# motor_board.net
KiCad netlist of a schematic drawn in EAGLE
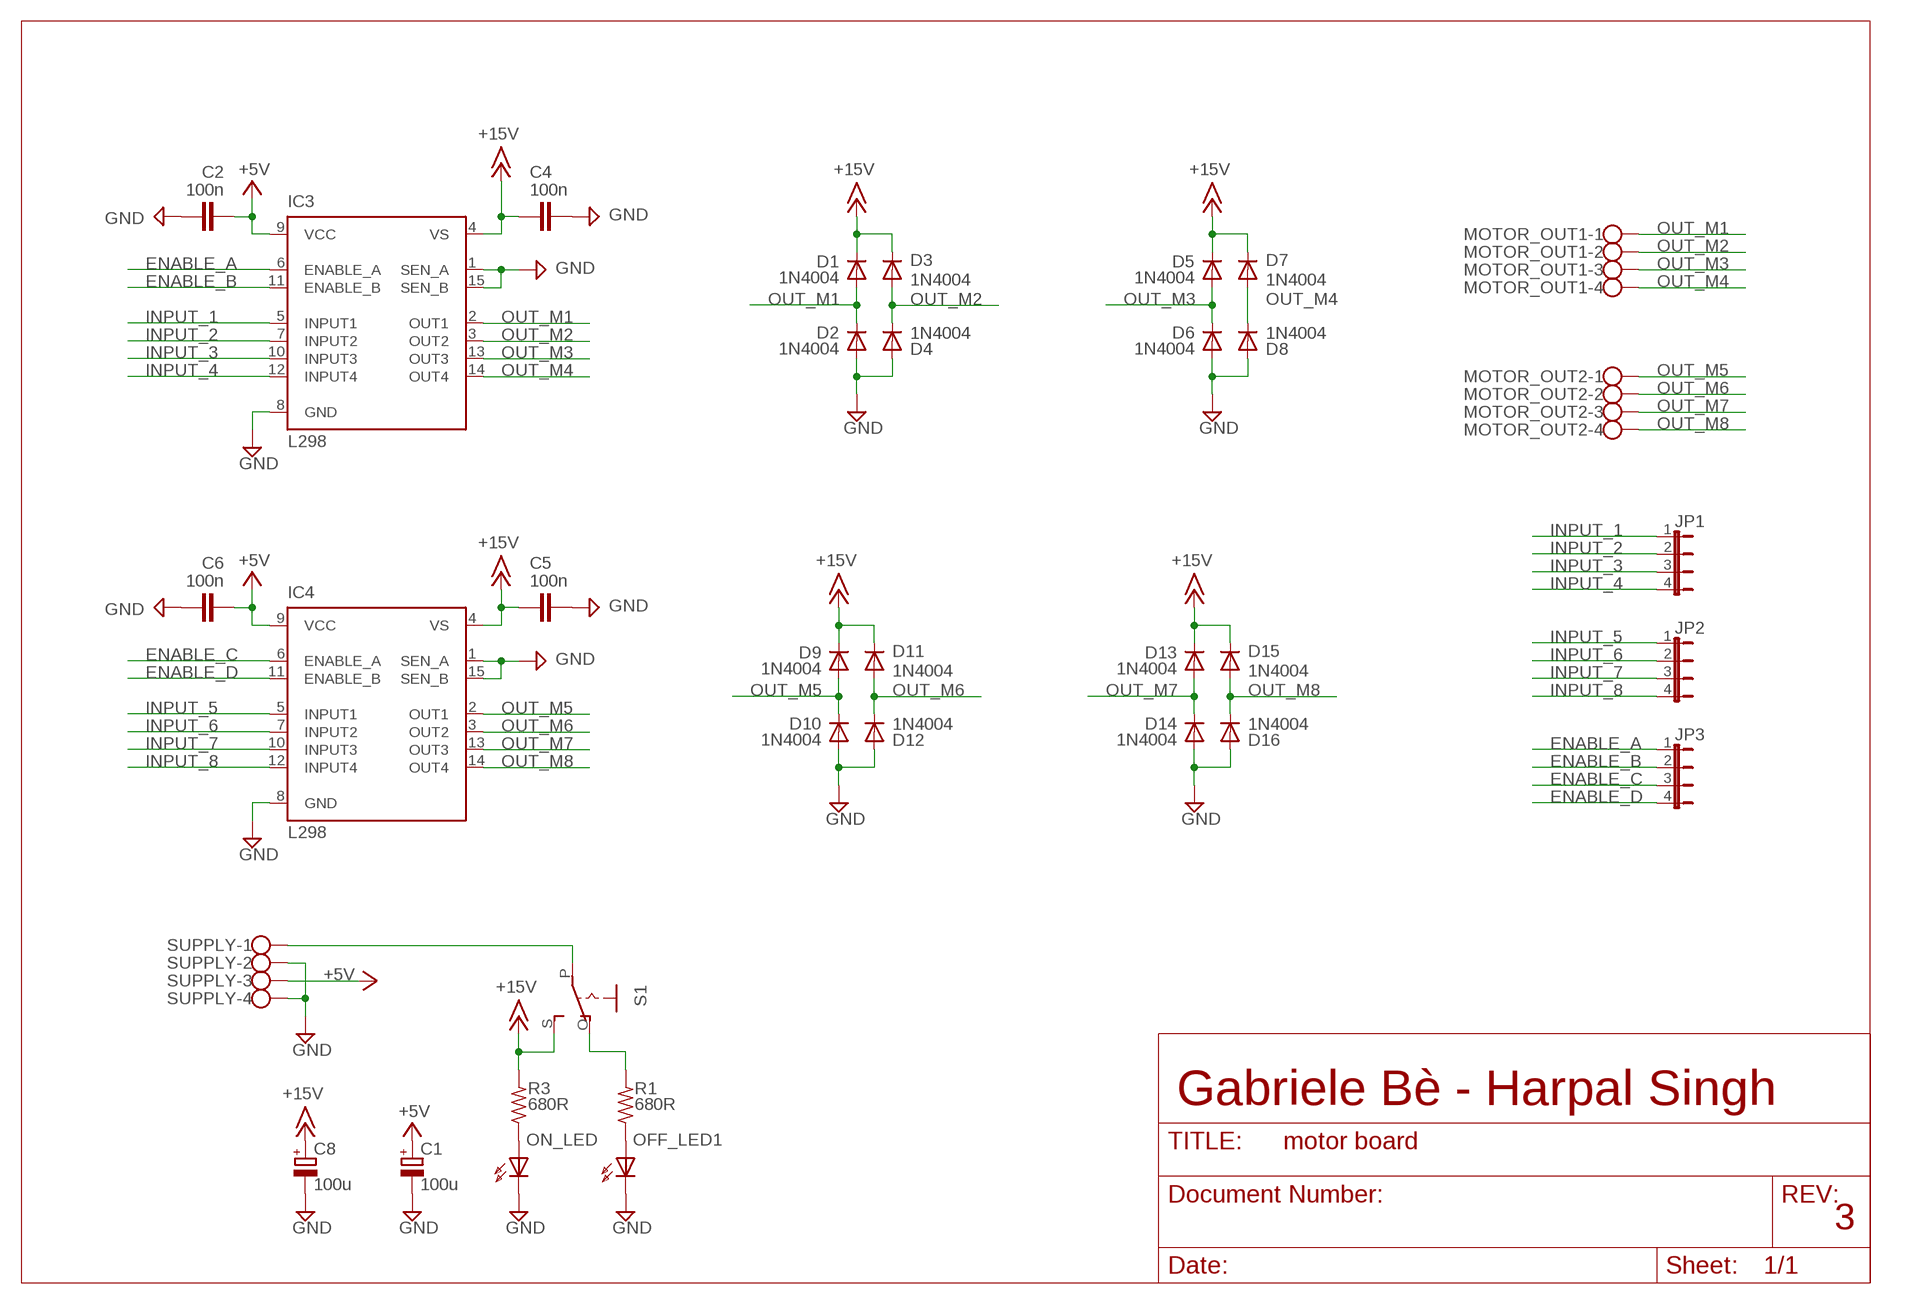
[diagram p0: schematic, sheet 1]

(export (version "E")
  (design (tool "Eeschema 10.0.6"))
  (components
    (comp (ref "C1")
      (value "100u")
      (footprint "eagle-import:E2,5-7")
      (libsource (lib "eagle-import") (part "CPOL-EUE2.5-7"))
    )
    (comp (ref "C2")
      (value "100n")
      (footprint "eagle-import:C050-024X044")
      (libsource (lib "eagle-import") (part "C-EU050-024X044"))
    )
    (comp (ref "C4")
      (value "100n")
      (footprint "eagle-import:C050-024X044")
      (libsource (lib "eagle-import") (part "C-EU050-024X044"))
    )
    (comp (ref "C5")
      (value "100n")
      (footprint "eagle-import:C050-024X044")
      (libsource (lib "eagle-import") (part "C-EU050-024X044"))
    )
    (comp (ref "C6")
      (value "100n")
      (footprint "eagle-import:C050-024X044")
      (libsource (lib "eagle-import") (part "C-EU050-024X044"))
    )
    (comp (ref "C8")
      (value "100u")
      (footprint "eagle-import:E2,5-7")
      (libsource (lib "eagle-import") (part "CPOL-EUE2.5-7"))
    )
    (comp (ref "D1")
      (value "1N4004")
      (footprint "eagle-import:DO41-10")
      (libsource (lib "eagle-import") (part "1N4004"))
    )
    (comp (ref "D2")
      (value "1N4004")
      (footprint "eagle-import:DO41-10")
      (libsource (lib "eagle-import") (part "1N4004"))
    )
    (comp (ref "D3")
      (value "1N4004")
      (footprint "eagle-import:DO41-10")
      (libsource (lib "eagle-import") (part "1N4004"))
    )
    (comp (ref "D4")
      (value "1N4004")
      (footprint "eagle-import:DO41-10")
      (libsource (lib "eagle-import") (part "1N4004"))
    )
    (comp (ref "D5")
      (value "1N4004")
      (footprint "eagle-import:DO41-10")
      (libsource (lib "eagle-import") (part "1N4004"))
    )
    (comp (ref "D6")
      (value "1N4004")
      (footprint "eagle-import:DO41-10")
      (libsource (lib "eagle-import") (part "1N4004"))
    )
    (comp (ref "D7")
      (value "1N4004")
      (footprint "eagle-import:DO41-10")
      (libsource (lib "eagle-import") (part "1N4004"))
    )
    (comp (ref "D8")
      (value "1N4004")
      (footprint "eagle-import:DO41-10")
      (libsource (lib "eagle-import") (part "1N4004"))
    )
    (comp (ref "D9")
      (value "1N4004")
      (footprint "eagle-import:DO41-10")
      (libsource (lib "eagle-import") (part "1N4004"))
    )
    (comp (ref "D10")
      (value "1N4004")
      (footprint "eagle-import:DO41-10")
      (libsource (lib "eagle-import") (part "1N4004"))
    )
    (comp (ref "D11")
      (value "1N4004")
      (footprint "eagle-import:DO41-10")
      (libsource (lib "eagle-import") (part "1N4004"))
    )
    (comp (ref "D12")
      (value "1N4004")
      (footprint "eagle-import:DO41-10")
      (libsource (lib "eagle-import") (part "1N4004"))
    )
    (comp (ref "D13")
      (value "1N4004")
      (footprint "eagle-import:DO41-10")
      (libsource (lib "eagle-import") (part "1N4004"))
    )
    (comp (ref "D14")
      (value "1N4004")
      (footprint "eagle-import:DO41-10")
      (libsource (lib "eagle-import") (part "1N4004"))
    )
    (comp (ref "D15")
      (value "1N4004")
      (footprint "eagle-import:DO41-10")
      (libsource (lib "eagle-import") (part "1N4004"))
    )
    (comp (ref "D16")
      (value "1N4004")
      (footprint "eagle-import:DO41-10")
      (libsource (lib "eagle-import") (part "1N4004"))
    )
    (comp (ref "IC3")
      (value "L298")
      (footprint "eagle-import:MULTIWATT-15")
      (libsource (lib "eagle-import") (part "L298"))
    )
    (comp (ref "IC4")
      (value "L298")
      (footprint "eagle-import:MULTIWATT-15")
      (libsource (lib "eagle-import") (part "L298"))
    )
    (comp (ref "JP1")
      (value "JP4E")
      (footprint "eagle-import:JP4")
      (libsource (lib "eagle-import") (part "JP4E"))
    )
    (comp (ref "JP2")
      (value "JP4E")
      (footprint "eagle-import:JP4")
      (libsource (lib "eagle-import") (part "JP4E"))
    )
    (comp (ref "JP3")
      (value "JP4E")
      (footprint "eagle-import:JP4")
      (libsource (lib "eagle-import") (part "JP4E"))
    )
    (comp (ref "MOTOR_OUT1")
      (value "W237-4")
      (footprint "eagle-import:W237-4")
      (libsource (lib "eagle-import") (part "W237-4"))
    )
    (comp (ref "MOTOR_OUT2")
      (value "W237-4")
      (footprint "eagle-import:W237-4")
      (libsource (lib "eagle-import") (part "W237-4"))
    )
    (comp (ref "OFF_LED1")
      (value "HLMP6")
      (footprint "eagle-import:HLMP6")
      (fields (field (name "MF") "AGILENT TECHNOLOGIES") (field (name "MPN") "HLMP-6500"))
      (libsource (lib "eagle-import") (part "HLMP6"))
    )
    (comp (ref "ON_LED")
      (value "HLMP6")
      (footprint "eagle-import:HLMP6")
      (fields (field (name "MF") "AGILENT TECHNOLOGIES") (field (name "MPN") "HLMP-6500"))
      (libsource (lib "eagle-import") (part "HLMP6"))
    )
    (comp (ref "R1")
      (value "680R")
      (footprint "eagle-import:0207_10")
      (libsource (lib "eagle-import") (part "R-US_0207/10"))
    )
    (comp (ref "R3")
      (value "680R")
      (footprint "eagle-import:0207_10")
      (libsource (lib "eagle-import") (part "R-US_0207/10"))
    )
    (comp (ref "S1")
      (value "EG1218S")
      (footprint "eagle-import:EG1218")
      (libsource (lib "eagle-import") (part "EG1218S"))
    )
    (comp (ref "SUPPLY")
      (value "W237-4")
      (footprint "eagle-import:W237-4")
      (libsource (lib "eagle-import") (part "W237-4"))
    )
  )
  (nets
    (net (code "1") (name "+5V") (class "Default")
      (node (ref "C1") (pin "+") (pinfunction "+_+") (pintype "passive"))
      (node (ref "C2") (pin "2") (pinfunction "2_2") (pintype "passive"))
      (node (ref "C6") (pin "2") (pinfunction "2_2") (pintype "passive"))
      (node (ref "IC3") (pin "9") (pinfunction "VCC_9") (pintype "power_in"))
      (node (ref "IC4") (pin "9") (pinfunction "VCC_9") (pintype "power_in"))
      (node (ref "SUPPLY") (pin "3") (pinfunction "KL_3") (pintype "passive"))
    )
    (net (code "2") (name "+15V") (class "Default")
      (node (ref "C4") (pin "1") (pinfunction "1_1") (pintype "passive"))
      (node (ref "C5") (pin "1") (pinfunction "1_1") (pintype "passive"))
      (node (ref "C8") (pin "+") (pinfunction "+_+") (pintype "passive"))
      (node (ref "D1") (pin "C") (pinfunction "C_C") (pintype "passive"))
      (node (ref "D11") (pin "C") (pinfunction "C_C") (pintype "passive"))
      (node (ref "D13") (pin "C") (pinfunction "C_C") (pintype "passive"))
      (node (ref "D15") (pin "C") (pinfunction "C_C") (pintype "passive"))
      (node (ref "D3") (pin "C") (pinfunction "C_C") (pintype "passive"))
      (node (ref "D5") (pin "C") (pinfunction "C_C") (pintype "passive"))
      (node (ref "D7") (pin "C") (pinfunction "C_C") (pintype "passive"))
      (node (ref "D9") (pin "C") (pinfunction "C_C") (pintype "passive"))
      (node (ref "IC3") (pin "4") (pinfunction "VS_4") (pintype "power_in"))
      (node (ref "IC4") (pin "4") (pinfunction "VS_4") (pintype "power_in"))
      (node (ref "R3") (pin "2") (pinfunction "2_2") (pintype "passive"))
      (node (ref "S1") (pin "S") (pinfunction "S_S") (pintype "passive"))
    )
    (net (code "3") (name "/ENABLE_A") (class "Default")
      (node (ref "IC3") (pin "6") (pinfunction "ENABLE_A_6") (pintype "input"))
      (node (ref "JP3") (pin "1") (pinfunction "1_1") (pintype "passive"))
    )
    (net (code "4") (name "/ENABLE_B") (class "Default")
      (node (ref "IC3") (pin "11") (pinfunction "ENABLE_B_11") (pintype "input"))
      (node (ref "JP3") (pin "2") (pinfunction "2_2") (pintype "passive"))
    )
    (net (code "5") (name "/ENABLE_C") (class "Default")
      (node (ref "IC4") (pin "6") (pinfunction "ENABLE_A_6") (pintype "input"))
      (node (ref "JP3") (pin "3") (pinfunction "3_3") (pintype "passive"))
    )
    (net (code "6") (name "/ENABLE_D") (class "Default")
      (node (ref "IC4") (pin "11") (pinfunction "ENABLE_B_11") (pintype "input"))
      (node (ref "JP3") (pin "4") (pinfunction "4_4") (pintype "passive"))
    )
    (net (code "7") (name "/INPUT_1") (class "Default")
      (node (ref "IC3") (pin "5") (pinfunction "INPUT1_5") (pintype "input"))
      (node (ref "JP1") (pin "1") (pinfunction "1_1") (pintype "passive"))
    )
    (net (code "8") (name "/INPUT_2") (class "Default")
      (node (ref "IC3") (pin "7") (pinfunction "INPUT2_7") (pintype "input"))
      (node (ref "JP1") (pin "2") (pinfunction "2_2") (pintype "passive"))
    )
    (net (code "9") (name "/INPUT_3") (class "Default")
      (node (ref "IC3") (pin "10") (pinfunction "INPUT3_10") (pintype "input"))
      (node (ref "JP1") (pin "3") (pinfunction "3_3") (pintype "passive"))
    )
    (net (code "10") (name "/INPUT_4") (class "Default")
      (node (ref "IC3") (pin "12") (pinfunction "INPUT4_12") (pintype "input"))
      (node (ref "JP1") (pin "4") (pinfunction "4_4") (pintype "passive"))
    )
    (net (code "11") (name "/INPUT_5") (class "Default")
      (node (ref "IC4") (pin "5") (pinfunction "INPUT1_5") (pintype "input"))
      (node (ref "JP2") (pin "1") (pinfunction "1_1") (pintype "passive"))
    )
    (net (code "12") (name "/INPUT_6") (class "Default")
      (node (ref "IC4") (pin "7") (pinfunction "INPUT2_7") (pintype "input"))
      (node (ref "JP2") (pin "2") (pinfunction "2_2") (pintype "passive"))
    )
    (net (code "13") (name "/INPUT_7") (class "Default")
      (node (ref "IC4") (pin "10") (pinfunction "INPUT3_10") (pintype "input"))
      (node (ref "JP2") (pin "3") (pinfunction "3_3") (pintype "passive"))
    )
    (net (code "14") (name "/INPUT_8") (class "Default")
      (node (ref "IC4") (pin "12") (pinfunction "INPUT4_12") (pintype "input"))
      (node (ref "JP2") (pin "4") (pinfunction "4_4") (pintype "passive"))
    )
    (net (code "15") (name "/OUT_M1") (class "Default")
      (node (ref "D1") (pin "A") (pinfunction "A_A") (pintype "passive"))
      (node (ref "D2") (pin "C") (pinfunction "C_C") (pintype "passive"))
      (node (ref "IC3") (pin "2") (pinfunction "OUT1_2") (pintype "output"))
      (node (ref "MOTOR_OUT1") (pin "1") (pinfunction "KL_1") (pintype "passive"))
    )
    (net (code "16") (name "/OUT_M2") (class "Default")
      (node (ref "D3") (pin "A") (pinfunction "A_A") (pintype "passive"))
      (node (ref "D4") (pin "C") (pinfunction "C_C") (pintype "passive"))
      (node (ref "IC3") (pin "3") (pinfunction "OUT2_3") (pintype "output"))
      (node (ref "MOTOR_OUT1") (pin "2") (pinfunction "KL_2") (pintype "passive"))
    )
    (net (code "17") (name "/OUT_M3") (class "Default")
      (node (ref "D5") (pin "A") (pinfunction "A_A") (pintype "passive"))
      (node (ref "D6") (pin "C") (pinfunction "C_C") (pintype "passive"))
      (node (ref "IC3") (pin "13") (pinfunction "OUT3_13") (pintype "output"))
      (node (ref "MOTOR_OUT1") (pin "3") (pinfunction "KL_3") (pintype "passive"))
    )
    (net (code "18") (name "/OUT_M4") (class "Default")
      (node (ref "D7") (pin "A") (pinfunction "A_A") (pintype "passive"))
      (node (ref "D8") (pin "C") (pinfunction "C_C") (pintype "passive"))
      (node (ref "IC3") (pin "14") (pinfunction "OUT4_14") (pintype "output"))
      (node (ref "MOTOR_OUT1") (pin "4") (pinfunction "KL_4") (pintype "passive"))
    )
    (net (code "19") (name "/OUT_M5") (class "Default")
      (node (ref "D10") (pin "C") (pinfunction "C_C") (pintype "passive"))
      (node (ref "D9") (pin "A") (pinfunction "A_A") (pintype "passive"))
      (node (ref "IC4") (pin "2") (pinfunction "OUT1_2") (pintype "output"))
      (node (ref "MOTOR_OUT2") (pin "1") (pinfunction "KL_1") (pintype "passive"))
    )
    (net (code "20") (name "/OUT_M6") (class "Default")
      (node (ref "D11") (pin "A") (pinfunction "A_A") (pintype "passive"))
      (node (ref "D12") (pin "C") (pinfunction "C_C") (pintype "passive"))
      (node (ref "IC4") (pin "3") (pinfunction "OUT2_3") (pintype "output"))
      (node (ref "MOTOR_OUT2") (pin "2") (pinfunction "KL_2") (pintype "passive"))
    )
    (net (code "21") (name "/OUT_M7") (class "Default")
      (node (ref "D13") (pin "A") (pinfunction "A_A") (pintype "passive"))
      (node (ref "D14") (pin "C") (pinfunction "C_C") (pintype "passive"))
      (node (ref "IC4") (pin "13") (pinfunction "OUT3_13") (pintype "output"))
      (node (ref "MOTOR_OUT2") (pin "3") (pinfunction "KL_3") (pintype "passive"))
    )
    (net (code "22") (name "/OUT_M8") (class "Default")
      (node (ref "D15") (pin "A") (pinfunction "A_A") (pintype "passive"))
      (node (ref "D16") (pin "C") (pinfunction "C_C") (pintype "passive"))
      (node (ref "IC4") (pin "14") (pinfunction "OUT4_14") (pintype "output"))
      (node (ref "MOTOR_OUT2") (pin "4") (pinfunction "KL_4") (pintype "passive"))
    )
    (net (code "23") (name "GND") (class "Default")
      (node (ref "C1") (pin "-") (pinfunction "-_-") (pintype "passive"))
      (node (ref "C2") (pin "1") (pinfunction "1_1") (pintype "passive"))
      (node (ref "C4") (pin "2") (pinfunction "2_2") (pintype "passive"))
      (node (ref "C5") (pin "2") (pinfunction "2_2") (pintype "passive"))
      (node (ref "C6") (pin "1") (pinfunction "1_1") (pintype "passive"))
      (node (ref "C8") (pin "-") (pinfunction "-_-") (pintype "passive"))
      (node (ref "D10") (pin "A") (pinfunction "A_A") (pintype "passive"))
      (node (ref "D12") (pin "A") (pinfunction "A_A") (pintype "passive"))
      (node (ref "D14") (pin "A") (pinfunction "A_A") (pintype "passive"))
      (node (ref "D16") (pin "A") (pinfunction "A_A") (pintype "passive"))
      (node (ref "D2") (pin "A") (pinfunction "A_A") (pintype "passive"))
      (node (ref "D4") (pin "A") (pinfunction "A_A") (pintype "passive"))
      (node (ref "D6") (pin "A") (pinfunction "A_A") (pintype "passive"))
      (node (ref "D8") (pin "A") (pinfunction "A_A") (pintype "passive"))
      (node (ref "IC3") (pin "1") (pinfunction "SEN_A_1") (pintype "input"))
      (node (ref "IC3") (pin "15") (pinfunction "SEN_B_15") (pintype "input"))
      (node (ref "IC3") (pin "8") (pinfunction "GND_8") (pintype "power_in"))
      (node (ref "IC4") (pin "1") (pinfunction "SEN_A_1") (pintype "input"))
      (node (ref "IC4") (pin "15") (pinfunction "SEN_B_15") (pintype "input"))
      (node (ref "IC4") (pin "8") (pinfunction "GND_8") (pintype "power_in"))
      (node (ref "OFF_LED1") (pin "K") (pinfunction "K_K") (pintype "passive"))
      (node (ref "ON_LED") (pin "K") (pinfunction "K_K") (pintype "passive"))
      (node (ref "SUPPLY") (pin "2") (pinfunction "KL_2") (pintype "passive"))
      (node (ref "SUPPLY") (pin "4") (pinfunction "KL_4") (pintype "passive"))
    )
    (net (code "24") (name "Net-(OFF_LED1-PadA)") (class "Default")
      (node (ref "OFF_LED1") (pin "A") (pinfunction "A_A") (pintype "passive"))
      (node (ref "R1") (pin "1") (pinfunction "1_1") (pintype "passive"))
    )
    (net (code "25") (name "Net-(ON_LED-PadA)") (class "Default")
      (node (ref "ON_LED") (pin "A") (pinfunction "A_A") (pintype "passive"))
      (node (ref "R3") (pin "1") (pinfunction "1_1") (pintype "passive"))
    )
    (net (code "26") (name "Net-(R1-Pad2)") (class "Default")
      (node (ref "R1") (pin "2") (pinfunction "2_2") (pintype "passive"))
      (node (ref "S1") (pin "O") (pinfunction "O_O") (pintype "passive"))
    )
    (net (code "27") (name "Net-(SUPPLYA-KL)") (class "Default")
      (node (ref "S1") (pin "P") (pinfunction "P_P") (pintype "passive"))
      (node (ref "SUPPLY") (pin "1") (pinfunction "KL_1") (pintype "passive"))
    )
  )
)
